# LcsNodes-Main-Controller-Board-A_02_07.net
KiCad netlist of a schematic drawn in EasyEDA
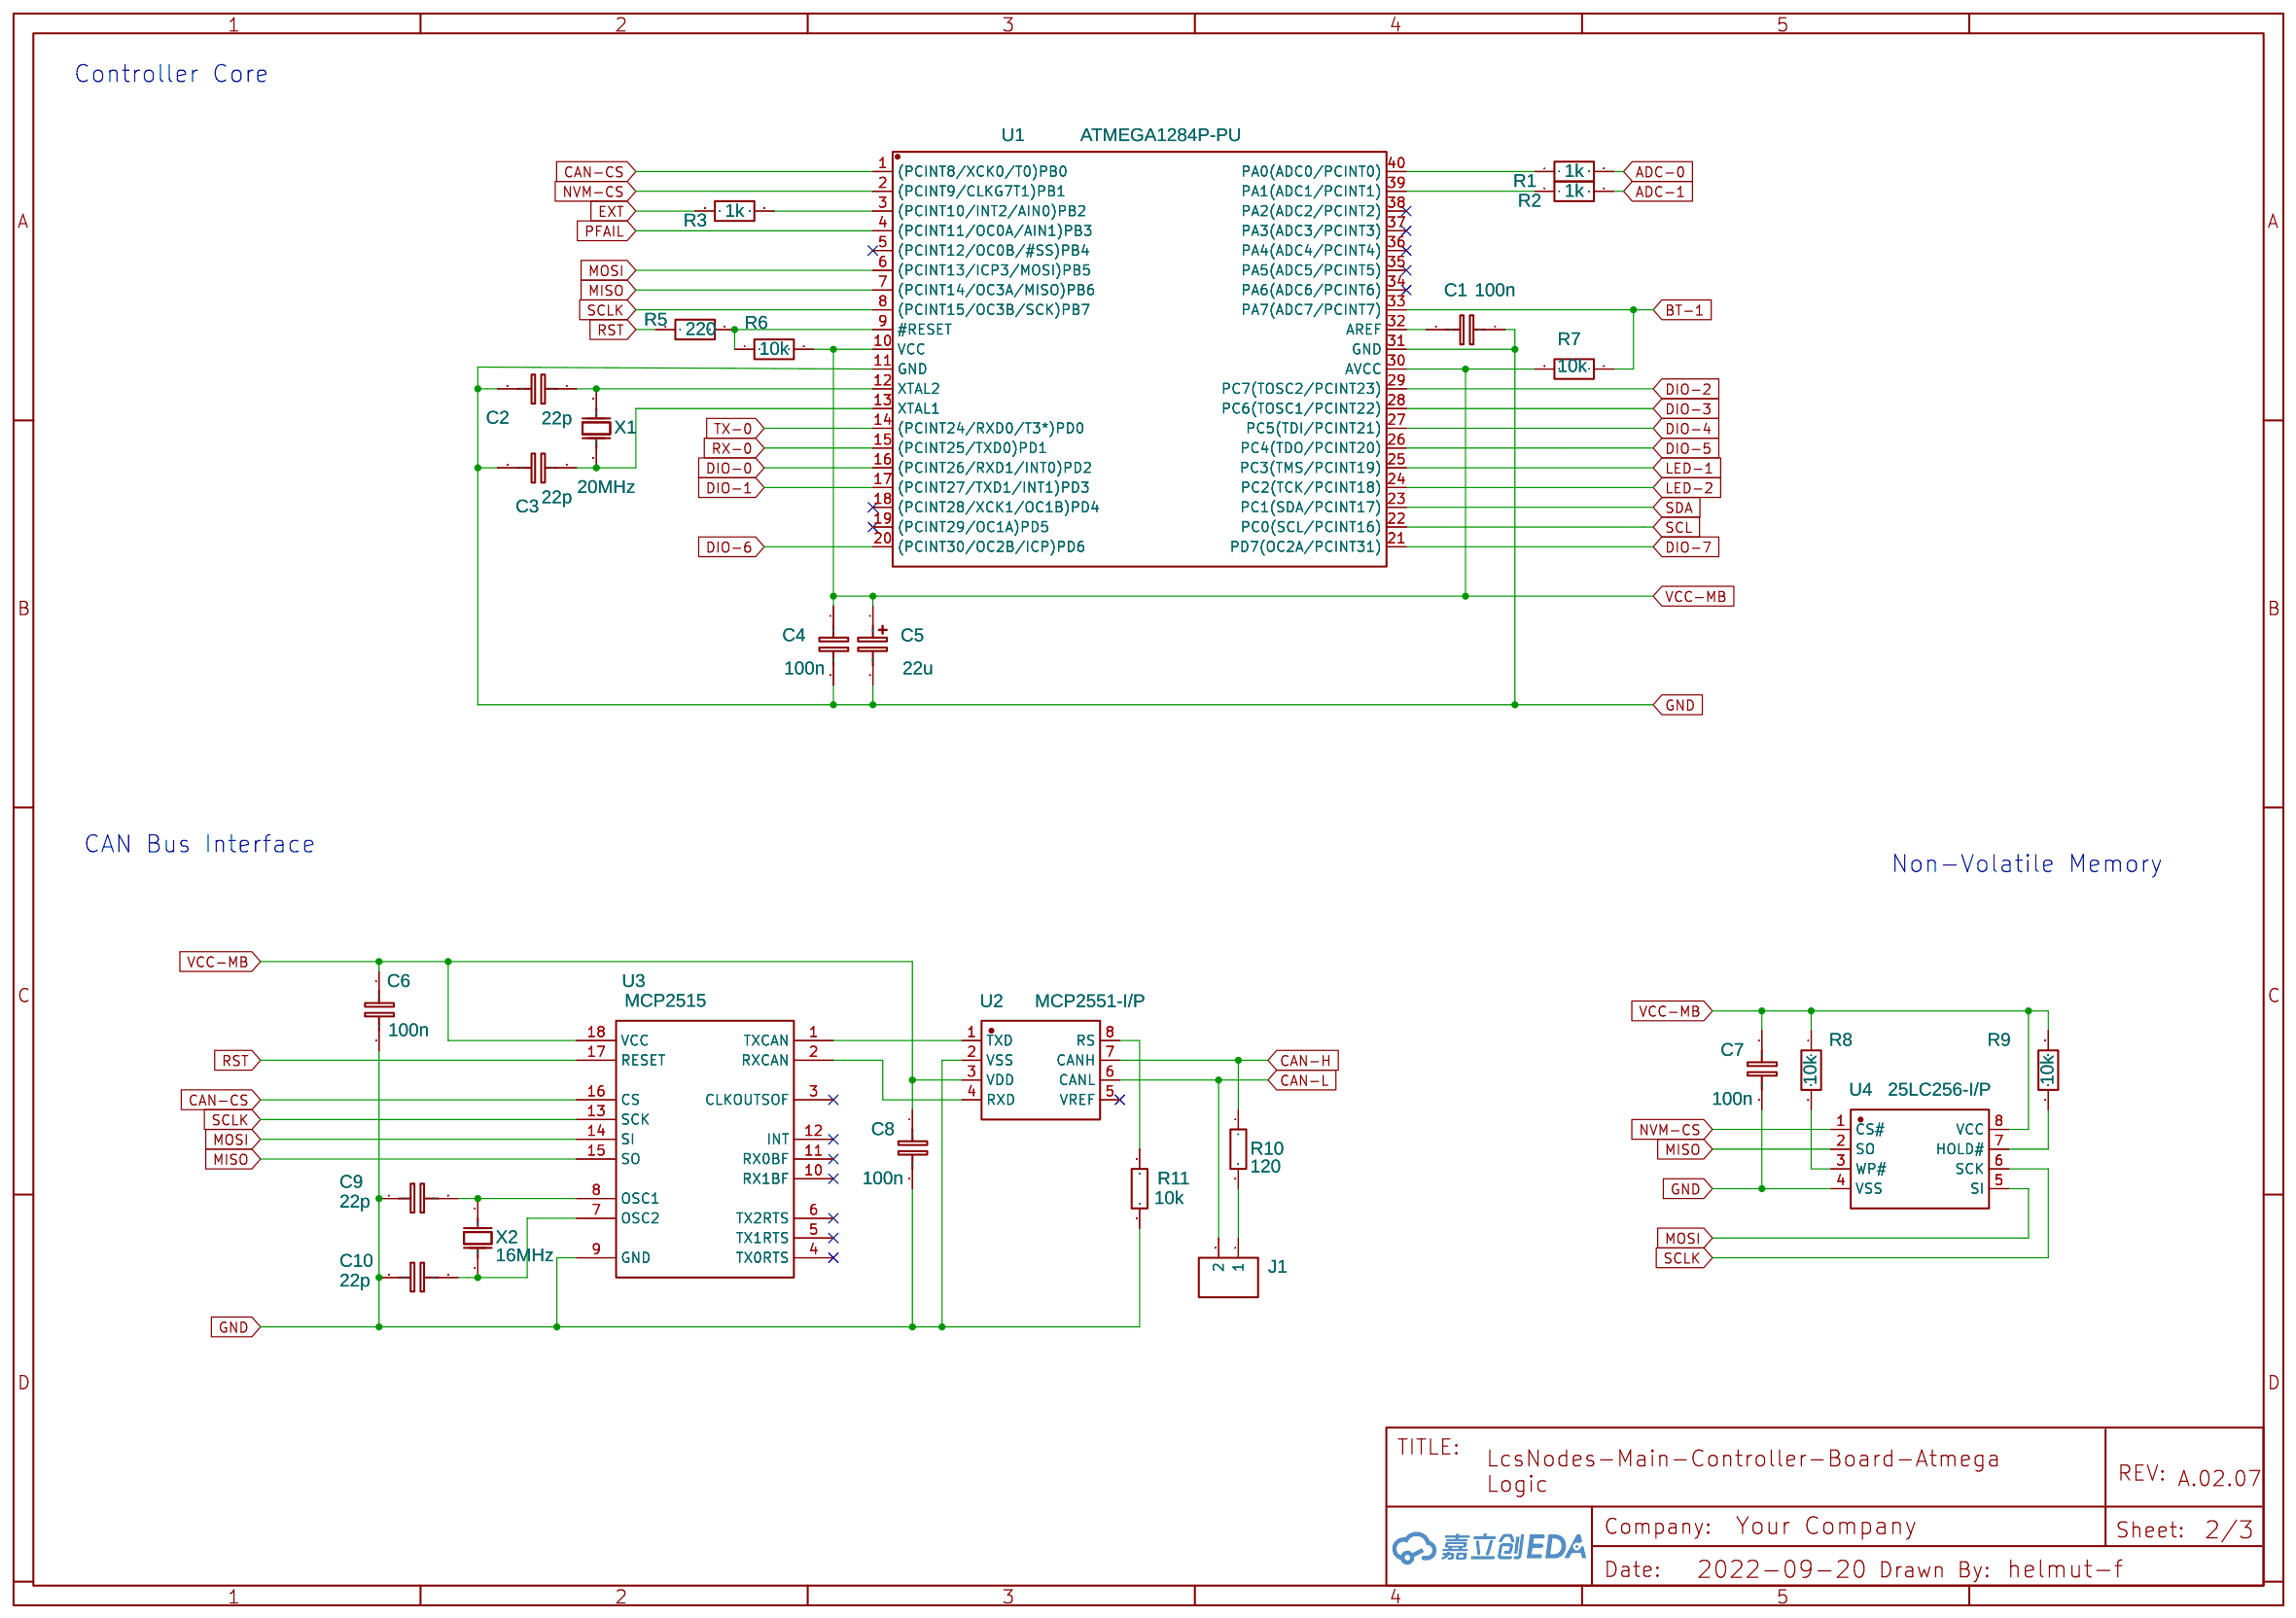
[diagram p0: Controller, CAN, NVM]
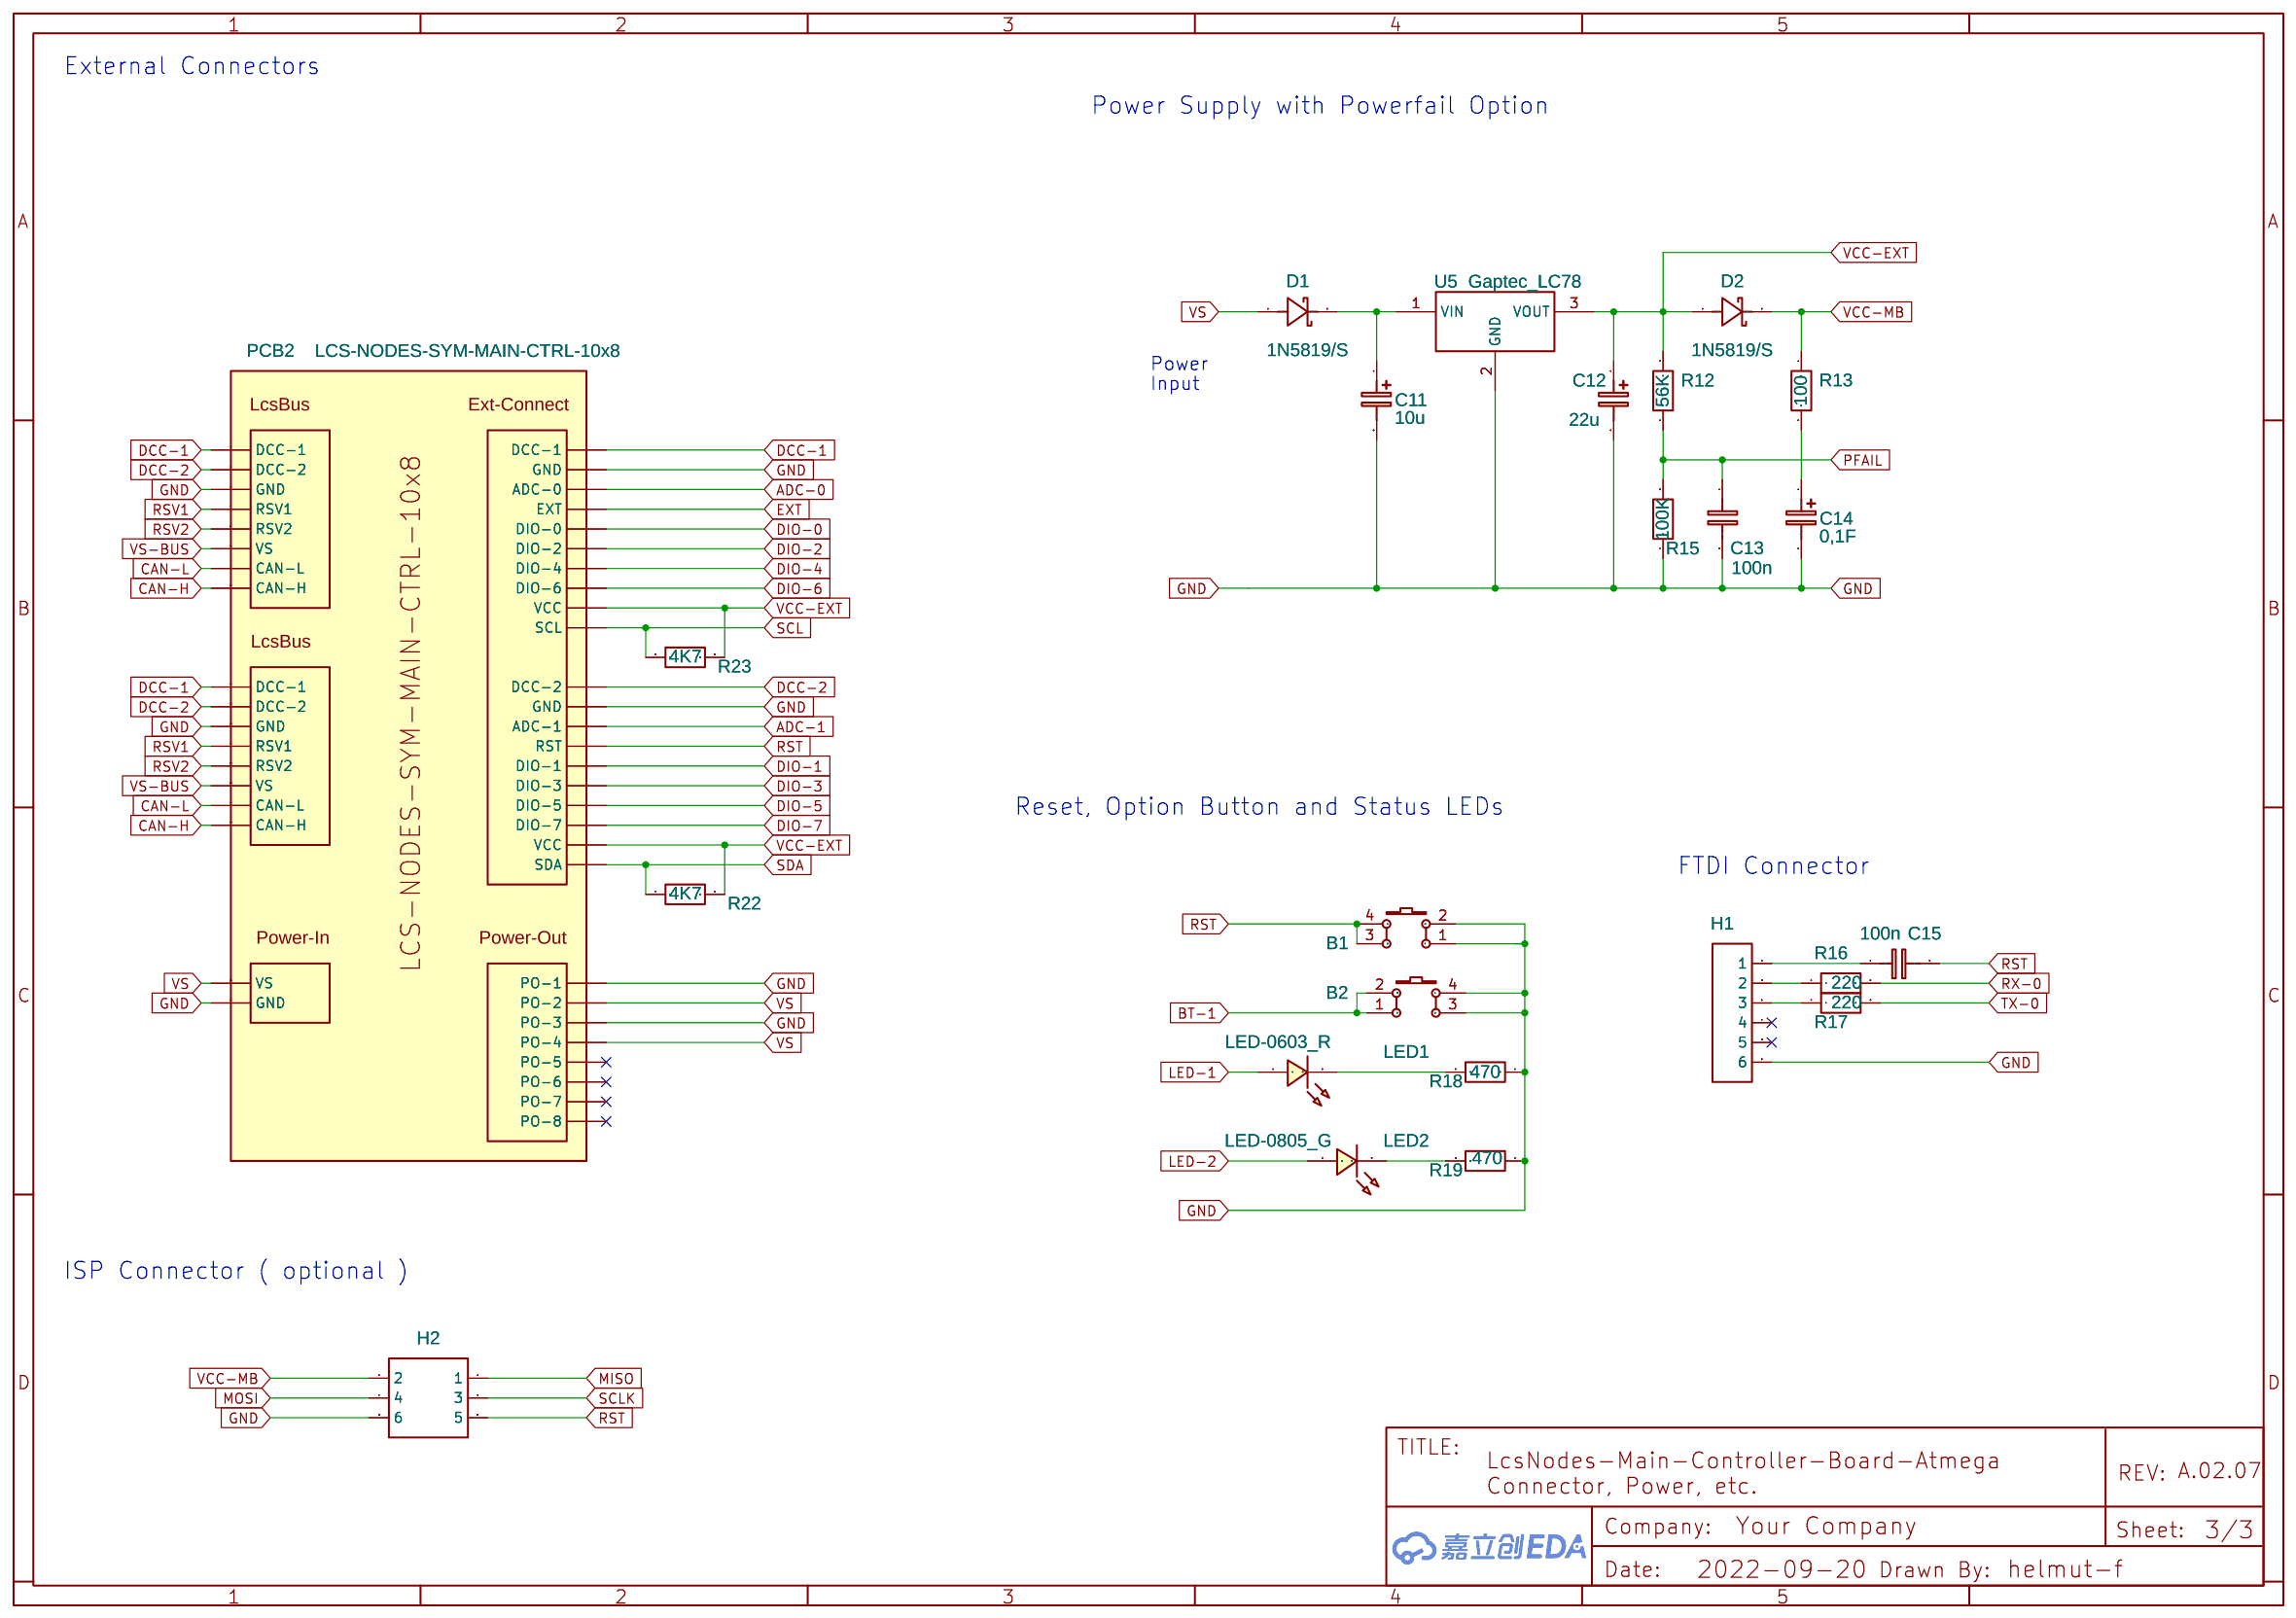
[diagram p1: Connector LCS, FTDI, ISP, Power Supply]
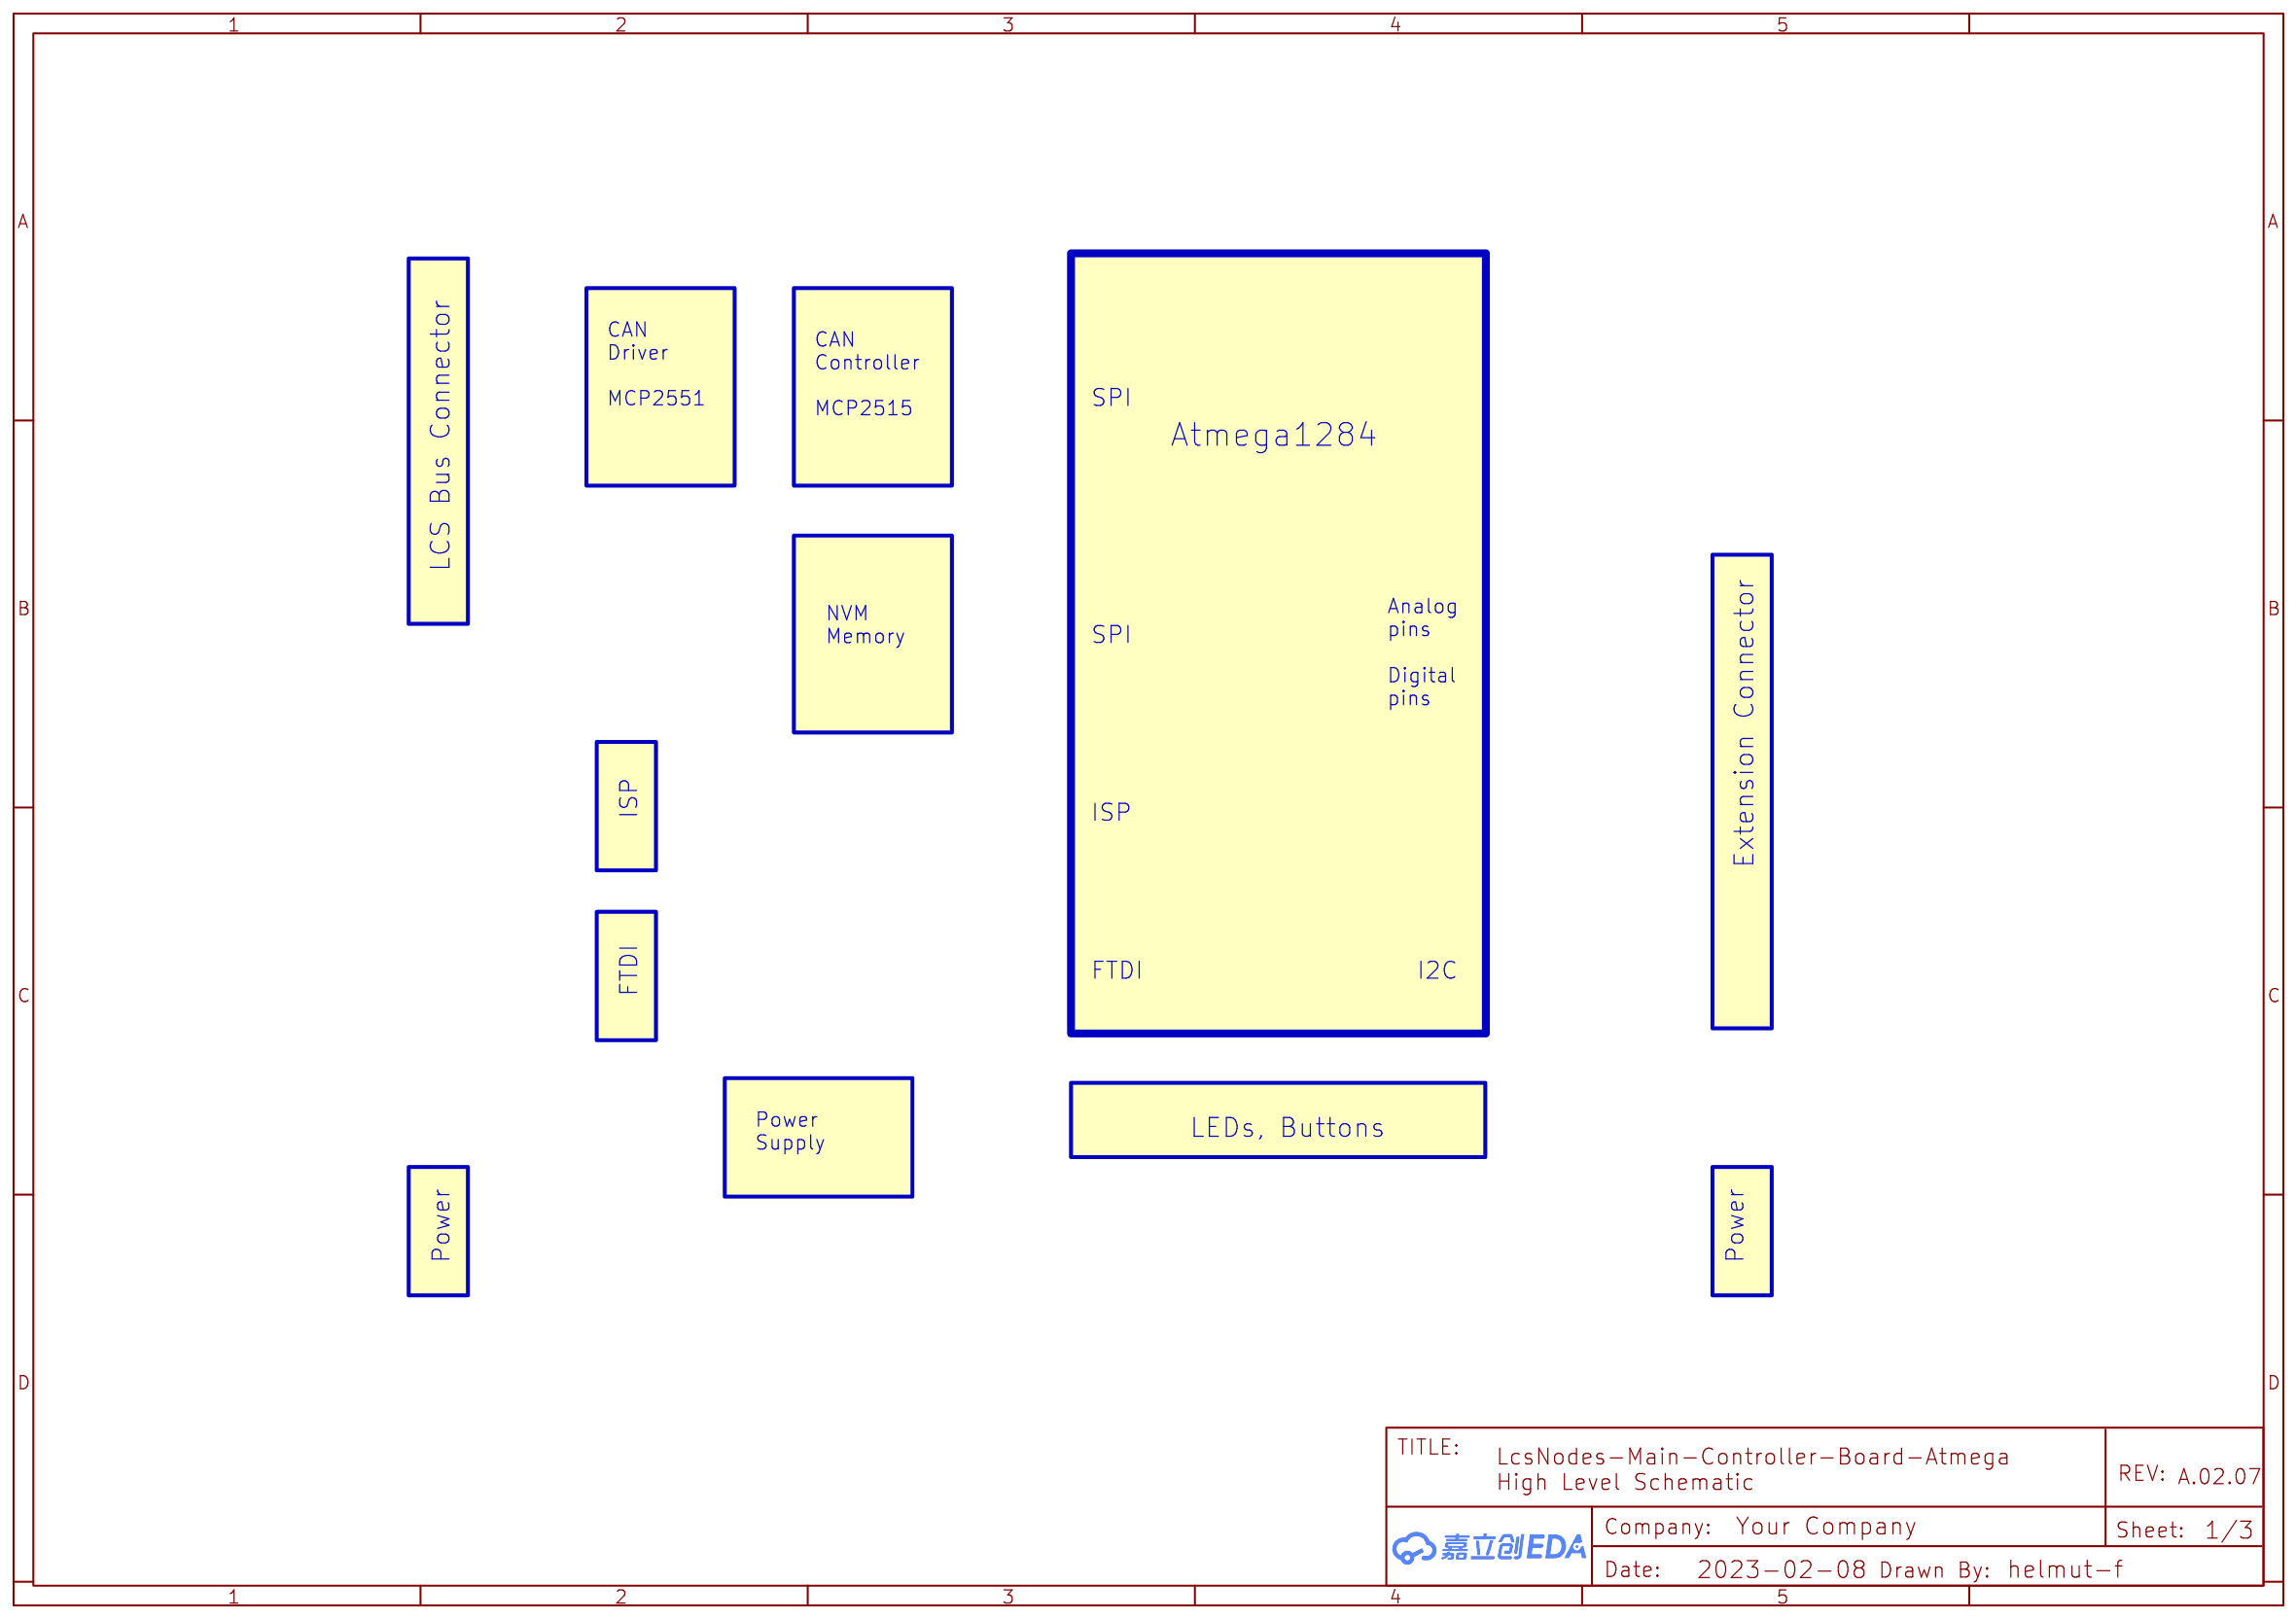
[diagram p2: Block Diagram]

(export (version "E")
  (design (tool "Eeschema 10.0.6"))
  (components
    (comp (ref "C1") (value "100n") (libsource (lib "") (part "C_RAD-0.1_EU")))
    (comp (ref "C2") (value "22p") (libsource (lib "") (part "C_0603_EU_3")))
    (comp (ref "C3") (value "22p") (libsource (lib "") (part "C_0603_EU_3")))
    (comp (ref "C4") (value "100n") (libsource (lib "") (part "C_0603_EU_1")))
    (comp (ref "C5") (value "22u") (libsource (lib "") (part "CE_TH_D4.0×F1.5_EU")))
    (comp (ref "C6") (value "100n") (libsource (lib "") (part "C_0603_EU_1")))
    (comp (ref "C7") (value "100n") (libsource (lib "") (part "C_0603_EU_2")))
    (comp (ref "C8") (value "100n") (libsource (lib "") (part "C_0603_EU_1")))
    (comp (ref "C9") (value "22p") (libsource (lib "") (part "C_0603_EU")))
    (comp (ref "C10") (value "22p") (libsource (lib "") (part "C_0603_EU")))
    (comp (ref "J1") (value "HDR-M-2.54_1x2") (libsource (lib "") (part "HDR-M-2.54_1x2")))
    (comp (ref "R1") (value "1k") (libsource (lib "") (part "R_AXIAL-0.3_EU")))
    (comp (ref "R2") (value "1k") (libsource (lib "") (part "R_AXIAL-0.3_EU")))
    (comp (ref "R3") (value "1k") (libsource (lib "") (part "R_AXIAL-0.3_EU")))
    (comp (ref "R5") (value "220") (libsource (lib "") (part "R_AXIAL-0.3_EU")))
    (comp (ref "R6") (value "10k") (libsource (lib "") (part "R_AXIAL-0.3_EU")))
    (comp (ref "R7") (value "10k") (libsource (lib "") (part "R_AXIAL-0.3_EU_2")))
    (comp (ref "R8") (value "10k") (libsource (lib "") (part "R_AXIAL-0.3_EU_3")))
    (comp (ref "R9") (value "10k") (libsource (lib "") (part "R_AXIAL-0.3_EU_1")))
    (comp (ref "R10") (value "120") (libsource (lib "") (part "RESISTOR-AXIAL-0.1")))
    (comp (ref "R11") (value "10k") (libsource (lib "") (part "RESISTOR-AXIAL-0.1")))
    (comp (ref "U1")
      (value "ATMEGA1284P-PU")
      (fields (field (name "Manufacturer") "Microchip Tech"))
      (libsource (lib "") (part "ATMEGA1284P-PU"))
    )
    (comp (ref "U2")
      (value "MCP2551-I/P")
      (fields (field (name "Manufacturer") "Microchip Tech"))
      (libsource (lib "") (part "MCP2551-I/P"))
    )
    (comp (ref "U3")
      (value "MCP2515")
      (fields (field (name "Manufacturer") "Microchip"))
      (libsource (lib "") (part "MCP2515"))
    )
    (comp (ref "U4")
      (value "25LC256-I/P")
      (fields (field (name "Manufacturer") "Microchip Tech"))
      (libsource (lib "") (part "25LC256-I/P"))
    )
    (comp (ref "X1")
      (value "20MHz")
      (fields (field (name "Manufacturer Part") "X49SM16MSD2SI") (field (name "Manufacturer") "YXC"))
      (libsource (lib "") (part "X49SM16MSD2SI"))
    )
    (comp (ref "X2")
      (value "16MHz")
      (fields (field (name "Manufacturer Part") "X49SM16MSD2SI") (field (name "Manufacturer") "YXC"))
      (libsource (lib "") (part "X49SM16MSD2SI"))
    )
    (comp (ref "B1")
      (value "Reset")
      (fields
        (field (name "BOM_Manufacturer Part") "K2-1102DP-E4SW-04")
        (field (name "BOM_Supplier Part") "C136684")
      )
      (libsource (lib "") (part "K4-6×6_TH"))
    )
    (comp (ref "B2")
      (value "Opt")
      (fields
        (field (name "BOM_Manufacturer Part") "K2-1102DP-E4SW-04")
        (field (name "BOM_Supplier Part") "C136684")
      )
      (libsource (lib "") (part "K4-6×6_TH_1"))
    )
    (comp (ref "C11") (value "10u") (libsource (lib "") (part "CE_SMD_D5.0×H5.5_EU")))
    (comp (ref "C12") (value "22u") (libsource (lib "") (part "CE_SMD_D5.0×H5.5_EU")))
    (comp (ref "C13") (value "100n") (libsource (lib "") (part "C_RAD-0.2_EU")))
    (comp (ref "C14") (value "0,1F") (libsource (lib "") (part "C_Tan_SMD_A_EU")))
    (comp (ref "C15") (value "100n") (libsource (lib "") (part "C_0603_EU")))
    (comp (ref "D1")
      (value "1N5819/S")
      (fields (field (name "BOM_Supplier Part") "C9900003833"))
      (libsource (lib "") (part "1N5819/S"))
    )
    (comp (ref "D2")
      (value "1N5819/S")
      (fields (field (name "BOM_Supplier Part") "C9900003833"))
      (libsource (lib "") (part "1N5819/S"))
    )
    (comp (ref "H1")
      (value "HDR-F-2.54_1x6")
      (fields (field (name "BOM_Supplier Part") "C40877"))
      (libsource (lib "") (part "HDR-F-2.54_1x6"))
    )
    (comp (ref "H2")
      (value "HDR-F-2.54_2x3")
      (fields (field (name "BOM_Supplier Part") "C65114"))
      (libsource (lib "") (part "HDR-F-2.54_2x3"))
    )
    (comp (ref "LED1")
      (value "LED-0603_R")
      (fields
        (field (name "BOM_Manufacturer Part") "19-217/R6C-AL1M2VY/3T")
        (field (name "BOM_Supplier Part") "C72044")
      )
      (libsource (lib "") (part "LED-0603_R"))
    )
    (comp (ref "LED2")
      (value "LED-0805_G")
      (fields (field (name "BOM_Manufacturer Part") "NCD0805G1") (field (name "BOM_Supplier Part") "C84260"))
      (libsource (lib "") (part "LED-0805_G"))
    )
    (comp (ref "PCB2")
      (value "LCS-NODES-SYM-MAIN-CTRL-10x8")
      (libsource (lib "") (part "LCS-NODES-SYM-MAIN-CTRL-10x8"))
    )
    (comp (ref "R12") (value "56K") (libsource (lib "") (part "R_AXIAL-0.3_EU_1")))
    (comp (ref "R13") (value "100") (libsource (lib "") (part "R_AXIAL-0.3_EU_2")))
    (comp (ref "R15") (value "100K") (libsource (lib "") (part "R_AXIAL-0.3_EU_1")))
    (comp (ref "R16") (value "220") (libsource (lib "") (part "R_AXIAL-0.3_EU")))
    (comp (ref "R17") (value "220") (libsource (lib "") (part "R_AXIAL-0.3_EU")))
    (comp (ref "R18") (value "470") (libsource (lib "") (part "R_0805_EU")))
    (comp (ref "R19") (value "470") (libsource (lib "") (part "R_0805_EU")))
    (comp (ref "R22") (value "4K7") (libsource (lib "") (part "R_AXIAL-0.3_EU")))
    (comp (ref "R23") (value "4K7") (libsource (lib "") (part "R_AXIAL-0.3_EU")))
    (comp (ref "U5") (value "Gaptec_LC78") (libsource (lib "") (part "Gaptec_LC78")))
  )
  (nets
    (net (code "1") (name "ADC-0") (class "Default")
      (node (ref "PCB2") (pin "32") (pinfunction "ADC-0_32") (pintype "unspecified"))
      (node (ref "R1") (pin "2") (pinfunction "2_2") (pintype "unspecified"))
    )
    (net (code "2") (name "ADC-1") (class "Default")
      (node (ref "PCB2") (pin "42") (pinfunction "ADC-1_42") (pintype "unspecified"))
      (node (ref "R2") (pin "2") (pinfunction "2_2") (pintype "unspecified"))
    )
    (net (code "3") (name "BT-1") (class "Default")
      (node (ref "B2") (pin "1") (pinfunction "1_1") (pintype "unspecified"))
      (node (ref "B2") (pin "2") (pinfunction "2_2") (pintype "unspecified"))
      (node (ref "R7") (pin "1") (pinfunction "1_1") (pintype "unspecified"))
      (node (ref "U1") (pin "33") (pinfunction "PA7(ADC7/PCINT7)_33") (pintype "unspecified"))
    )
    (net (code "4") (name "CAN-CS") (class "Default")
      (node (ref "U1") (pin "1") (pinfunction "(PCINT8/XCK0/T0)PB0_1") (pintype "unspecified"))
      (node (ref "U3") (pin "16") (pinfunction "CS_16") (pintype "unspecified"))
    )
    (net (code "5") (name "CAN-H") (class "Default")
      (node (ref "PCB2") (pin "18") (pinfunction "CAN-H_18") (pintype "unspecified"))
      (node (ref "PCB2") (pin "8") (pinfunction "CAN-H_8") (pintype "unspecified"))
      (node (ref "R10") (pin "1") (pinfunction "1_1") (pintype "input"))
      (node (ref "U2") (pin "7") (pinfunction "CANH_7") (pintype "unspecified"))
    )
    (net (code "6") (name "CAN-L") (class "Default")
      (node (ref "J1") (pin "2") (pinfunction "2_2") (pintype "unspecified"))
      (node (ref "PCB2") (pin "17") (pinfunction "CAN-L_17") (pintype "unspecified"))
      (node (ref "PCB2") (pin "7") (pinfunction "CAN-L_7") (pintype "unspecified"))
      (node (ref "U2") (pin "6") (pinfunction "CANL_6") (pintype "unspecified"))
    )
    (net (code "7") (name "DCC-1") (class "Default")
      (node (ref "PCB2") (pin "1") (pinfunction "DCC-1_1") (pintype "unspecified"))
      (node (ref "PCB2") (pin "11") (pinfunction "DCC-1_11") (pintype "unspecified"))
      (node (ref "PCB2") (pin "30") (pinfunction "DCC-1_30") (pintype "unspecified"))
    )
    (net (code "8") (name "DCC-2") (class "Default")
      (node (ref "PCB2") (pin "12") (pinfunction "DCC-2_12") (pintype "unspecified"))
      (node (ref "PCB2") (pin "2") (pinfunction "DCC-2_2") (pintype "unspecified"))
      (node (ref "PCB2") (pin "40") (pinfunction "DCC-2_40") (pintype "unspecified"))
    )
    (net (code "9") (name "DIO-0") (class "Default")
      (node (ref "PCB2") (pin "34") (pinfunction "DIO-0_34") (pintype "unspecified"))
      (node (ref "U1") (pin "16") (pinfunction "(PCINT26/RXD1/INT0)PD2_16") (pintype "unspecified"))
    )
    (net (code "10") (name "DIO-1") (class "Default")
      (node (ref "PCB2") (pin "44") (pinfunction "DIO-1_44") (pintype "unspecified"))
      (node (ref "U1") (pin "17") (pinfunction "(PCINT27/TXD1/INT1)PD3_17") (pintype "unspecified"))
    )
    (net (code "11") (name "DIO-2") (class "Default")
      (node (ref "PCB2") (pin "35") (pinfunction "DIO-2_35") (pintype "unspecified"))
      (node (ref "U1") (pin "29") (pinfunction "PC7(TOSC2/PCINT23)_29") (pintype "unspecified"))
    )
    (net (code "12") (name "DIO-3") (class "Default")
      (node (ref "PCB2") (pin "45") (pinfunction "DIO-3_45") (pintype "unspecified"))
      (node (ref "U1") (pin "28") (pinfunction "PC6(TOSC1/PCINT22)_28") (pintype "unspecified"))
    )
    (net (code "13") (name "DIO-4") (class "Default")
      (node (ref "PCB2") (pin "36") (pinfunction "DIO-4_36") (pintype "unspecified"))
      (node (ref "U1") (pin "27") (pinfunction "PC5(TDI/PCINT21)_27") (pintype "unspecified"))
    )
    (net (code "14") (name "DIO-5") (class "Default")
      (node (ref "PCB2") (pin "46") (pinfunction "DIO-5_46") (pintype "unspecified"))
      (node (ref "U1") (pin "26") (pinfunction "PC4(TDO/PCINT20)_26") (pintype "unspecified"))
    )
    (net (code "15") (name "DIO-6") (class "Default")
      (node (ref "PCB2") (pin "37") (pinfunction "DIO-6_37") (pintype "unspecified"))
      (node (ref "U1") (pin "20") (pinfunction "(PCINT30/OC2B/ICP)PD6_20") (pintype "unspecified"))
    )
    (net (code "16") (name "DIO-7") (class "Default")
      (node (ref "PCB2") (pin "47") (pinfunction "DIO-7_47") (pintype "unspecified"))
      (node (ref "U1") (pin "21") (pinfunction "PD7(OC2A/PCINT31)_21") (pintype "unspecified"))
    )
    (net (code "17") (name "EXT") (class "Default")
      (node (ref "PCB2") (pin "33") (pinfunction "EXT_33") (pintype "unspecified"))
      (node (ref "R3") (pin "1") (pinfunction "1_1") (pintype "unspecified"))
    )
    (net (code "18") (name "GND") (class "Default")
      (node (ref "B1") (pin "1") (pinfunction "1_1") (pintype "unspecified"))
      (node (ref "B1") (pin "2") (pinfunction "2_2") (pintype "unspecified"))
      (node (ref "B2") (pin "3") (pinfunction "3_3") (pintype "unspecified"))
      (node (ref "B2") (pin "4") (pinfunction "4_4") (pintype "unspecified"))
      (node (ref "C1") (pin "1") (pinfunction "1_1") (pintype "unspecified"))
      (node (ref "C10") (pin "1") (pinfunction "1_1") (pintype "unspecified"))
      (node (ref "C11") (pin "2") (pinfunction "2_2") (pintype "unspecified"))
      (node (ref "C12") (pin "2") (pinfunction "2_2") (pintype "unspecified"))
      (node (ref "C13") (pin "2") (pinfunction "2_2") (pintype "unspecified"))
      (node (ref "C14") (pin "2") (pinfunction "2_2") (pintype "unspecified"))
      (node (ref "C2") (pin "2") (pinfunction "2_2") (pintype "unspecified"))
      (node (ref "C3") (pin "2") (pinfunction "2_2") (pintype "unspecified"))
      (node (ref "C4") (pin "2") (pinfunction "2_2") (pintype "unspecified"))
      (node (ref "C5") (pin "2") (pinfunction "2_2") (pintype "unspecified"))
      (node (ref "C6") (pin "2") (pinfunction "2_2") (pintype "unspecified"))
      (node (ref "C7") (pin "2") (pinfunction "2_2") (pintype "unspecified"))
      (node (ref "C8") (pin "2") (pinfunction "2_2") (pintype "unspecified"))
      (node (ref "C9") (pin "1") (pinfunction "1_1") (pintype "unspecified"))
      (node (ref "H1") (pin "6") (pinfunction "6_6") (pintype "input"))
      (node (ref "H2") (pin "6") (pinfunction "6_6") (pintype "input"))
      (node (ref "PCB2") (pin "13") (pinfunction "GND_13") (pintype "unspecified"))
      (node (ref "PCB2") (pin "21") (pinfunction "GND_21") (pintype "unspecified"))
      (node (ref "PCB2") (pin "3") (pinfunction "GND_3") (pintype "unspecified"))
      (node (ref "PCB2") (pin "31") (pinfunction "GND_31") (pintype "unspecified"))
      (node (ref "PCB2") (pin "41") (pinfunction "GND_41") (pintype "unspecified"))
      (node (ref "PCB2") (pin "50") (pinfunction "PO-1_50") (pintype "unspecified"))
      (node (ref "PCB2") (pin "51") (pinfunction "PO-3_51") (pintype "unspecified"))
      (node (ref "R11") (pin "2") (pinfunction "2_2") (pintype "input"))
      (node (ref "R15") (pin "1") (pinfunction "1_1") (pintype "unspecified"))
      (node (ref "R18") (pin "1") (pinfunction "1_1") (pintype "unspecified"))
      (node (ref "R19") (pin "1") (pinfunction "1_1") (pintype "unspecified"))
      (node (ref "U1") (pin "11") (pinfunction "GND_11") (pintype "unspecified"))
      (node (ref "U1") (pin "31") (pinfunction "GND_31") (pintype "unspecified"))
      (node (ref "U2") (pin "2") (pinfunction "VSS_2") (pintype "unspecified"))
      (node (ref "U3") (pin "9") (pinfunction "GND_9") (pintype "passive"))
      (node (ref "U4") (pin "4") (pinfunction "VSS_4") (pintype "unspecified"))
      (node (ref "U5") (pin "2") (pinfunction "GND_2") (pintype "unspecified"))
    )
    (net (code "19") (name "LED-1") (class "Default")
      (node (ref "LED1") (pin "1") (pinfunction "1_1") (pintype "unspecified"))
      (node (ref "U1") (pin "25") (pinfunction "PC3(TMS/PCINT19)_25") (pintype "unspecified"))
    )
    (net (code "20") (name "LED-2") (class "Default")
      (node (ref "LED2") (pin "1") (pinfunction "1_1") (pintype "unspecified"))
      (node (ref "U1") (pin "24") (pinfunction "PC2(TCK/PCINT18)_24") (pintype "unspecified"))
    )
    (net (code "21") (name "MISO") (class "Default")
      (node (ref "H2") (pin "1") (pinfunction "1_1") (pintype "input"))
      (node (ref "U1") (pin "7") (pinfunction "(PCINT14/OC3A/MISO)PB6_7") (pintype "unspecified"))
      (node (ref "U3") (pin "15") (pinfunction "SO_15") (pintype "output"))
      (node (ref "U4") (pin "2") (pinfunction "SO_2") (pintype "unspecified"))
    )
    (net (code "22") (name "MOSI") (class "Default")
      (node (ref "H2") (pin "4") (pinfunction "4_4") (pintype "input"))
      (node (ref "U1") (pin "6") (pinfunction "(PCINT13/ICP3/MOSI)PB5_6") (pintype "unspecified"))
      (node (ref "U3") (pin "14") (pinfunction "SI_14") (pintype "unspecified"))
      (node (ref "U4") (pin "5") (pinfunction "SI_5") (pintype "unspecified"))
    )
    (net (code "23") (name "NVM-CS") (class "Default")
      (node (ref "U1") (pin "2") (pinfunction "(PCINT9/CLKG7T1)PB1_2") (pintype "unspecified"))
      (node (ref "U4") (pin "1") (pinfunction "CS#_1") (pintype "unspecified"))
    )
    (net (code "24") (name "Net-(C14-Pad1)") (class "Default")
      (node (ref "C14") (pin "1") (pinfunction "1_1") (pintype "unspecified"))
      (node (ref "R13") (pin "2") (pinfunction "2_2") (pintype "unspecified"))
    )
    (net (code "25") (name "Net-(C15-Pad1)") (class "Default")
      (node (ref "C15") (pin "1") (pinfunction "1_1") (pintype "unspecified"))
      (node (ref "H1") (pin "1") (pinfunction "1_1") (pintype "input"))
    )
    (net (code "26") (name "Net-(D1-K)") (class "Default")
      (node (ref "C11") (pin "1") (pinfunction "1_1") (pintype "unspecified"))
      (node (ref "D1") (pin "2") (pinfunction "K_2") (pintype "unspecified"))
      (node (ref "U5") (pin "1") (pinfunction "VIN_1") (pintype "unspecified"))
    )
    (net (code "27") (name "Net-(H1-Pad2)") (class "Default")
      (node (ref "H1") (pin "2") (pinfunction "2_2") (pintype "input"))
      (node (ref "R16") (pin "1") (pinfunction "1_1") (pintype "unspecified"))
    )
    (net (code "28") (name "Net-(H1-Pad3)") (class "Default")
      (node (ref "H1") (pin "3") (pinfunction "3_3") (pintype "input"))
      (node (ref "R17") (pin "1") (pinfunction "1_1") (pintype "unspecified"))
    )
    (net (code "29") (name "Net-(J1-Pad1)") (class "Default")
      (node (ref "J1") (pin "1") (pinfunction "1_1") (pintype "unspecified"))
      (node (ref "R10") (pin "2") (pinfunction "2_2") (pintype "input"))
    )
    (net (code "30") (name "Net-(LED1-Pad2)") (class "Default")
      (node (ref "LED1") (pin "2") (pinfunction "2_2") (pintype "unspecified"))
      (node (ref "R18") (pin "2") (pinfunction "2_2") (pintype "unspecified"))
    )
    (net (code "31") (name "Net-(LED2-Pad2)") (class "Default")
      (node (ref "LED2") (pin "2") (pinfunction "2_2") (pintype "unspecified"))
      (node (ref "R19") (pin "2") (pinfunction "2_2") (pintype "unspecified"))
    )
    (net (code "32") (name "Net-(U1-#RESET)") (class "Default")
      (node (ref "R5") (pin "2") (pinfunction "2_2") (pintype "unspecified"))
      (node (ref "R6") (pin "1") (pinfunction "1_1") (pintype "unspecified"))
      (node (ref "U1") (pin "9") (pinfunction "#RESET_9") (pintype "unspecified"))
    )
    (net (code "33") (name "Net-(U1-(PCINT10{slash}INT2{slash}AIN0)PB2)") (class "Default")
      (node (ref "R3") (pin "2") (pinfunction "2_2") (pintype "unspecified"))
      (node (ref "U1") (pin "3") (pinfunction "(PCINT10/INT2/AIN0)PB2_3") (pintype "unspecified"))
    )
    (net (code "34") (name "Net-(U1-AREF)") (class "Default")
      (node (ref "C1") (pin "2") (pinfunction "2_2") (pintype "unspecified"))
      (node (ref "U1") (pin "32") (pinfunction "AREF_32") (pintype "unspecified"))
    )
    (net (code "35") (name "Net-(U1-PA0(ADC0{slash}PCINT0))") (class "Default")
      (node (ref "R1") (pin "1") (pinfunction "1_1") (pintype "unspecified"))
      (node (ref "U1") (pin "40") (pinfunction "PA0(ADC0/PCINT0)_40") (pintype "unspecified"))
    )
    (net (code "36") (name "Net-(U1-PA1(ADC1{slash}PCINT1))") (class "Default")
      (node (ref "R2") (pin "1") (pinfunction "1_1") (pintype "unspecified"))
      (node (ref "U1") (pin "39") (pinfunction "PA1(ADC1/PCINT1)_39") (pintype "unspecified"))
    )
    (net (code "37") (name "Net-(U1-XTAL1)") (class "Default")
      (node (ref "C3") (pin "1") (pinfunction "1_1") (pintype "unspecified"))
      (node (ref "U1") (pin "13") (pinfunction "XTAL1_13") (pintype "unspecified"))
      (node (ref "X1") (pin "2") (pinfunction "OSC2_2") (pintype "input"))
    )
    (net (code "38") (name "Net-(U1-XTAL2)") (class "Default")
      (node (ref "C2") (pin "1") (pinfunction "1_1") (pintype "unspecified"))
      (node (ref "U1") (pin "12") (pinfunction "XTAL2_12") (pintype "unspecified"))
      (node (ref "X1") (pin "1") (pinfunction "OSC1_1") (pintype "input"))
    )
    (net (code "39") (name "Net-(U2-RS)") (class "Default")
      (node (ref "R11") (pin "1") (pinfunction "1_1") (pintype "input"))
      (node (ref "U2") (pin "8") (pinfunction "RS_8") (pintype "unspecified"))
    )
    (net (code "40") (name "Net-(U2-RXD)") (class "Default")
      (node (ref "U2") (pin "4") (pinfunction "RXD_4") (pintype "unspecified"))
      (node (ref "U3") (pin "2") (pinfunction "RXCAN_2") (pintype "unspecified"))
    )
    (net (code "41") (name "Net-(U2-TXD)") (class "Default")
      (node (ref "U2") (pin "1") (pinfunction "TXD_1") (pintype "unspecified"))
      (node (ref "U3") (pin "1") (pinfunction "TXCAN_1") (pintype "output"))
    )
    (net (code "42") (name "Net-(U3-OSC1)") (class "Default")
      (node (ref "C9") (pin "2") (pinfunction "2_2") (pintype "unspecified"))
      (node (ref "U3") (pin "8") (pinfunction "OSC1_8") (pintype "unspecified"))
      (node (ref "X2") (pin "1") (pinfunction "OSC1_1") (pintype "input"))
    )
    (net (code "43") (name "Net-(U3-OSC2)") (class "Default")
      (node (ref "C10") (pin "2") (pinfunction "2_2") (pintype "unspecified"))
      (node (ref "U3") (pin "7") (pinfunction "OSC2_7") (pintype "output"))
      (node (ref "X2") (pin "2") (pinfunction "OSC2_2") (pintype "input"))
    )
    (net (code "44") (name "Net-(U4-HOLD#)") (class "Default")
      (node (ref "R9") (pin "1") (pinfunction "1_1") (pintype "unspecified"))
      (node (ref "U4") (pin "7") (pinfunction "HOLD#_7") (pintype "unspecified"))
    )
    (net (code "45") (name "Net-(U4-WP#)") (class "Default")
      (node (ref "R8") (pin "2") (pinfunction "2_2") (pintype "unspecified"))
      (node (ref "U4") (pin "3") (pinfunction "WP#_3") (pintype "unspecified"))
    )
    (net (code "46") (name "PFAIL") (class "Default")
      (node (ref "C13") (pin "1") (pinfunction "1_1") (pintype "unspecified"))
      (node (ref "R12") (pin "1") (pinfunction "1_1") (pintype "unspecified"))
      (node (ref "R15") (pin "2") (pinfunction "2_2") (pintype "unspecified"))
      (node (ref "U1") (pin "4") (pinfunction "(PCINT11/OC0A/AIN1)PB3_4") (pintype "unspecified"))
    )
    (net (code "47") (name "RST") (class "Default")
      (node (ref "B1") (pin "3") (pinfunction "3_3") (pintype "unspecified"))
      (node (ref "B1") (pin "4") (pinfunction "4_4") (pintype "unspecified"))
      (node (ref "C15") (pin "2") (pinfunction "2_2") (pintype "unspecified"))
      (node (ref "H2") (pin "5") (pinfunction "5_5") (pintype "input"))
      (node (ref "PCB2") (pin "43") (pinfunction "RST_43") (pintype "unspecified"))
      (node (ref "R5") (pin "1") (pinfunction "1_1") (pintype "unspecified"))
      (node (ref "U3") (pin "17") (pinfunction "RESET_17") (pintype "unspecified"))
    )
    (net (code "48") (name "RSV1") (class "Default")
      (node (ref "PCB2") (pin "14") (pinfunction "RSV1_14") (pintype "unspecified"))
      (node (ref "PCB2") (pin "4") (pinfunction "RSV1_4") (pintype "unspecified"))
    )
    (net (code "49") (name "RSV2") (class "Default")
      (node (ref "PCB2") (pin "15") (pinfunction "RSV2_15") (pintype "unspecified"))
      (node (ref "PCB2") (pin "5") (pinfunction "RSV2_5") (pintype "unspecified"))
    )
    (net (code "50") (name "RX-0") (class "Default")
      (node (ref "R16") (pin "2") (pinfunction "2_2") (pintype "unspecified"))
      (node (ref "U1") (pin "15") (pinfunction "(PCINT25/TXD0)PD1_15") (pintype "unspecified"))
    )
    (net (code "51") (name "SCL") (class "Default")
      (node (ref "PCB2") (pin "39") (pinfunction "SCL_39") (pintype "unspecified"))
      (node (ref "R23") (pin "1") (pinfunction "1_1") (pintype "unspecified"))
      (node (ref "U1") (pin "22") (pinfunction "PC0(SCL/PCINT16)_22") (pintype "unspecified"))
    )
    (net (code "52") (name "SCLK") (class "Default")
      (node (ref "H2") (pin "3") (pinfunction "3_3") (pintype "input"))
      (node (ref "U1") (pin "8") (pinfunction "(PCINT15/OC3B/SCK)PB7_8") (pintype "unspecified"))
      (node (ref "U3") (pin "13") (pinfunction "SCK_13") (pintype "unspecified"))
      (node (ref "U4") (pin "6") (pinfunction "SCK_6") (pintype "unspecified"))
    )
    (net (code "53") (name "SDA") (class "Default")
      (node (ref "PCB2") (pin "49") (pinfunction "SDA_49") (pintype "unspecified"))
      (node (ref "R22") (pin "1") (pinfunction "1_1") (pintype "unspecified"))
      (node (ref "U1") (pin "23") (pinfunction "PC1(SDA/PCINT17)_23") (pintype "unspecified"))
    )
    (net (code "54") (name "TX-0") (class "Default")
      (node (ref "R17") (pin "2") (pinfunction "2_2") (pintype "unspecified"))
      (node (ref "U1") (pin "14") (pinfunction "(PCINT24/RXD0/T3*)PD0_14") (pintype "unspecified"))
    )
    (net (code "55") (name "VCC-EXT") (class "Default")
      (node (ref "C12") (pin "1") (pinfunction "1_1") (pintype "unspecified"))
      (node (ref "D2") (pin "1") (pinfunction "A_1") (pintype "unspecified"))
      (node (ref "PCB2") (pin "38") (pinfunction "VCC_38") (pintype "unspecified"))
      (node (ref "PCB2") (pin "48") (pinfunction "VCC_48") (pintype "unspecified"))
      (node (ref "R12") (pin "2") (pinfunction "2_2") (pintype "unspecified"))
      (node (ref "R22") (pin "2") (pinfunction "2_2") (pintype "unspecified"))
      (node (ref "R23") (pin "2") (pinfunction "2_2") (pintype "unspecified"))
      (node (ref "U5") (pin "3") (pinfunction "VOUT_3") (pintype "unspecified"))
    )
    (net (code "56") (name "VCC-MB") (class "Default")
      (node (ref "C4") (pin "1") (pinfunction "1_1") (pintype "unspecified"))
      (node (ref "C5") (pin "1") (pinfunction "1_1") (pintype "unspecified"))
      (node (ref "C6") (pin "1") (pinfunction "1_1") (pintype "unspecified"))
      (node (ref "C7") (pin "1") (pinfunction "1_1") (pintype "unspecified"))
      (node (ref "C8") (pin "1") (pinfunction "1_1") (pintype "unspecified"))
      (node (ref "D2") (pin "2") (pinfunction "K_2") (pintype "unspecified"))
      (node (ref "H2") (pin "2") (pinfunction "2_2") (pintype "input"))
      (node (ref "R13") (pin "1") (pinfunction "1_1") (pintype "unspecified"))
      (node (ref "R6") (pin "2") (pinfunction "2_2") (pintype "unspecified"))
      (node (ref "R7") (pin "2") (pinfunction "2_2") (pintype "unspecified"))
      (node (ref "R8") (pin "1") (pinfunction "1_1") (pintype "unspecified"))
      (node (ref "R9") (pin "2") (pinfunction "2_2") (pintype "unspecified"))
      (node (ref "U1") (pin "10") (pinfunction "VCC_10") (pintype "unspecified"))
      (node (ref "U1") (pin "30") (pinfunction "AVCC_30") (pintype "unspecified"))
      (node (ref "U2") (pin "3") (pinfunction "VDD_3") (pintype "unspecified"))
      (node (ref "U3") (pin "18") (pinfunction "VCC_18") (pintype "passive"))
      (node (ref "U4") (pin "8") (pinfunction "VCC_8") (pintype "unspecified"))
    )
    (net (code "57") (name "VS") (class "Default")
      (node (ref "D1") (pin "1") (pinfunction "A_1") (pintype "unspecified"))
      (node (ref "PCB2") (pin "20") (pinfunction "VS_20") (pintype "unspecified"))
      (node (ref "PCB2") (pin "54") (pinfunction "PO-2_54") (pintype "unspecified"))
      (node (ref "PCB2") (pin "55") (pinfunction "PO-4_55") (pintype "unspecified"))
    )
    (net (code "58") (name "VS-BUS") (class "Default")
      (node (ref "PCB2") (pin "16") (pinfunction "VS_16") (pintype "unspecified"))
      (node (ref "PCB2") (pin "6") (pinfunction "VS_6") (pintype "unspecified"))
    )
    (net (code "59") (name "unconnected-(H1-Pad4)") (class "Default")
      (node (ref "H1") (pin "4") (pinfunction "4_4") (pintype "input+no_connect"))
    )
    (net (code "60") (name "unconnected-(H1-Pad5)") (class "Default")
      (node (ref "H1") (pin "5") (pinfunction "5_5") (pintype "input+no_connect"))
    )
    (net (code "61") (name "unconnected-(PCB2-PO-5-Pad52)") (class "Default")
      (node (ref "PCB2") (pin "52") (pinfunction "PO-5_52") (pintype "unspecified+no_connect"))
    )
    (net (code "62") (name "unconnected-(PCB2-PO-6-Pad56)") (class "Default")
      (node (ref "PCB2") (pin "56") (pinfunction "PO-6_56") (pintype "unspecified+no_connect"))
    )
    (net (code "63") (name "unconnected-(PCB2-PO-7-Pad53)") (class "Default")
      (node (ref "PCB2") (pin "53") (pinfunction "PO-7_53") (pintype "unspecified+no_connect"))
    )
    (net (code "64") (name "unconnected-(PCB2-PO-8-Pad57)") (class "Default")
      (node (ref "PCB2") (pin "57") (pinfunction "PO-8_57") (pintype "unspecified+no_connect"))
    )
    (net (code "65") (name "unconnected-(U1-(PCINT12{slash}OC0B{slash}#SS)PB4-Pad5)") (class "Default")
      (node (ref "U1") (pin "5") (pinfunction "(PCINT12/OC0B/#SS)PB4_5") (pintype "unspecified+no_connect"))
    )
    (net (code "66") (name "unconnected-(U1-(PCINT28{slash}XCK1{slash}OC1B)PD4-Pad18)") (class "Default")
      (node (ref "U1") (pin "18") (pinfunction "(PCINT28/XCK1/OC1B)PD4_18") (pintype "unspecified+no_connect"))
    )
    (net (code "67") (name "unconnected-(U1-(PCINT29{slash}OC1A)PD5-Pad19)") (class "Default")
      (node (ref "U1") (pin "19") (pinfunction "(PCINT29/OC1A)PD5_19") (pintype "unspecified+no_connect"))
    )
    (net (code "68") (name "unconnected-(U1-PA2(ADC2{slash}PCINT2)-Pad38)") (class "Default")
      (node (ref "U1") (pin "38") (pinfunction "PA2(ADC2/PCINT2)_38") (pintype "unspecified+no_connect"))
    )
    (net (code "69") (name "unconnected-(U1-PA3(ADC3{slash}PCINT3)-Pad37)") (class "Default")
      (node (ref "U1") (pin "37") (pinfunction "PA3(ADC3/PCINT3)_37") (pintype "unspecified+no_connect"))
    )
    (net (code "70") (name "unconnected-(U1-PA4(ADC4{slash}PCINT4)-Pad36)") (class "Default")
      (node (ref "U1") (pin "36") (pinfunction "PA4(ADC4/PCINT4)_36") (pintype "unspecified+no_connect"))
    )
    (net (code "71") (name "unconnected-(U1-PA5(ADC5{slash}PCINT5)-Pad35)") (class "Default")
      (node (ref "U1") (pin "35") (pinfunction "PA5(ADC5/PCINT5)_35") (pintype "unspecified+no_connect"))
    )
    (net (code "72") (name "unconnected-(U1-PA6(ADC6{slash}PCINT6)-Pad34)") (class "Default")
      (node (ref "U1") (pin "34") (pinfunction "PA6(ADC6/PCINT6)_34") (pintype "unspecified+no_connect"))
    )
    (net (code "73") (name "unconnected-(U2-VREF-Pad5)") (class "Default")
      (node (ref "U2") (pin "5") (pinfunction "VREF_5") (pintype "unspecified+no_connect"))
    )
    (net (code "74") (name "unconnected-(U3-CLKOUTSOF-Pad3)") (class "Default")
      (node (ref "U3") (pin "3") (pinfunction "CLKOUTSOF_3") (pintype "output+no_connect"))
    )
    (net (code "75") (name "unconnected-(U3-INT-Pad12)") (class "Default")
      (node (ref "U3") (pin "12") (pinfunction "INT_12") (pintype "output+no_connect"))
    )
    (net (code "76") (name "unconnected-(U3-RX0BF-Pad11)") (class "Default")
      (node (ref "U3") (pin "11") (pinfunction "RX0BF_11") (pintype "output+no_connect"))
    )
    (net (code "77") (name "unconnected-(U3-RX1BF-Pad10)") (class "Default")
      (node (ref "U3") (pin "10") (pinfunction "RX1BF_10") (pintype "output+no_connect"))
    )
    (net (code "78") (name "unconnected-(U3-TX0RTS-Pad4)") (class "Default")
      (node (ref "U3") (pin "4") (pinfunction "TX0RTS_4") (pintype "unspecified+no_connect"))
    )
    (net (code "79") (name "unconnected-(U3-TX1RTS-Pad5)") (class "Default")
      (node (ref "U3") (pin "5") (pinfunction "TX1RTS_5") (pintype "unspecified+no_connect"))
    )
    (net (code "80") (name "unconnected-(U3-TX2RTS-Pad6)") (class "Default")
      (node (ref "U3") (pin "6") (pinfunction "TX2RTS_6") (pintype "unspecified+no_connect"))
    )
  )
)
